# Diagram.net
KiCad netlist of a schematic drawn in EAGLE
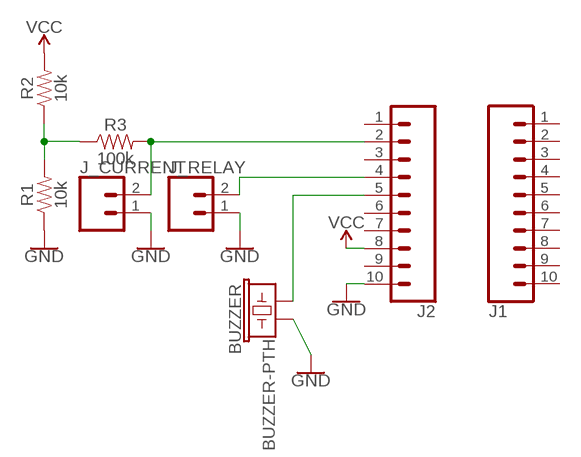
[diagram p0: schematic, sheet 1]

(export (version "E")
  (design (tool "Eeschema 10.0.6"))
  (components
    (comp (ref "BUZZER")
      (value "BUZZER-PTH")
      (footprint "eagle-import:BUZZER-12MM")
      (libsource (lib "eagle-import") (part "BUZZER-PTH"))
    )
    (comp (ref "J1")
      (value "CONN_10\"")
      (footprint "eagle-import:1X10")
      (libsource (lib "eagle-import") (part "CONN_10{dblquote}"))
    )
    (comp (ref "J2")
      (value "CONN_10\"")
      (footprint "eagle-import:1X10")
      (libsource (lib "eagle-import") (part "CONN_10{dblquote}"))
    )
    (comp (ref "J_CURRENT")
      (value "CONN_02")
      (footprint "eagle-import:1X02")
      (libsource (lib "eagle-import") (part "CONN_02"))
    )
    (comp (ref "J_RELAY")
      (value "CONN_02")
      (footprint "eagle-import:1X02")
      (libsource (lib "eagle-import") (part "CONN_02"))
    )
    (comp (ref "R1")
      (value "10k")
      (footprint "eagle-import:AXIAL-0.3")
      (libsource (lib "eagle-import") (part "1KOHM-HORIZ-1/4W-1%"))
    )
    (comp (ref "R2")
      (value "10k")
      (footprint "eagle-import:AXIAL-0.3")
      (libsource (lib "eagle-import") (part "1KOHM-HORIZ-1/4W-1%"))
    )
    (comp (ref "R3")
      (value "100k")
      (footprint "eagle-import:AXIAL-0.3")
      (libsource (lib "eagle-import") (part "1KOHM-HORIZ-1/4W-1%"))
    )
  )
  (nets
    (net (code "1") (name "GND") (class "Default")
      (node (ref "BUZZER") (pin "-") (pinfunction "2_-") (pintype "passive"))
      (node (ref "J2") (pin "10") (pinfunction "10_10") (pintype "passive"))
      (node (ref "J_CURRENT") (pin "1") (pinfunction "1_1") (pintype "passive"))
      (node (ref "J_RELAY") (pin "1") (pinfunction "1_1") (pintype "passive"))
      (node (ref "R1") (pin "P$1") (pinfunction "1_P$1") (pintype "passive"))
    )
    (net (code "2") (name "Net-(BUZZER-1)") (class "Default")
      (node (ref "BUZZER") (pin "+") (pinfunction "1_+") (pintype "passive"))
      (node (ref "J2") (pin "5") (pinfunction "5_5") (pintype "passive"))
    )
    (net (code "3") (name "Net-(J2-Pad4)") (class "Default")
      (node (ref "J2") (pin "4") (pinfunction "4_4") (pintype "passive"))
      (node (ref "J_RELAY") (pin "2") (pinfunction "2_2") (pintype "passive"))
    )
    (net (code "4") (name "Net-(R1-2)") (class "Default")
      (node (ref "R1") (pin "P$2") (pinfunction "2_P$2") (pintype "passive"))
      (node (ref "R2") (pin "P$1") (pinfunction "1_P$1") (pintype "passive"))
      (node (ref "R3") (pin "P$1") (pinfunction "1_P$1") (pintype "passive"))
    )
    (net (code "5") (name "Net-(R3-2)") (class "Default")
      (node (ref "J2") (pin "2") (pinfunction "2_2") (pintype "passive"))
      (node (ref "J_CURRENT") (pin "2") (pinfunction "2_2") (pintype "passive"))
      (node (ref "R3") (pin "P$2") (pinfunction "2_P$2") (pintype "passive"))
    )
    (net (code "6") (name "VCC") (class "Default")
      (node (ref "J2") (pin "8") (pinfunction "8_8") (pintype "passive"))
      (node (ref "R2") (pin "P$2") (pinfunction "2_P$2") (pintype "passive"))
    )
    (net (code "7") (name "unconnected-(J1-Pad1)") (class "Default")
      (node (ref "J1") (pin "1") (pinfunction "1_1") (pintype "passive"))
    )
    (net (code "8") (name "unconnected-(J1-Pad2)") (class "Default")
      (node (ref "J1") (pin "2") (pinfunction "2_2") (pintype "passive"))
    )
    (net (code "9") (name "unconnected-(J1-Pad3)") (class "Default")
      (node (ref "J1") (pin "3") (pinfunction "3_3") (pintype "passive"))
    )
    (net (code "10") (name "unconnected-(J1-Pad4)") (class "Default")
      (node (ref "J1") (pin "4") (pinfunction "4_4") (pintype "passive"))
    )
    (net (code "11") (name "unconnected-(J1-Pad5)") (class "Default")
      (node (ref "J1") (pin "5") (pinfunction "5_5") (pintype "passive"))
    )
    (net (code "12") (name "unconnected-(J1-Pad6)") (class "Default")
      (node (ref "J1") (pin "6") (pinfunction "6_6") (pintype "passive"))
    )
    (net (code "13") (name "unconnected-(J1-Pad7)") (class "Default")
      (node (ref "J1") (pin "7") (pinfunction "7_7") (pintype "passive"))
    )
    (net (code "14") (name "unconnected-(J1-Pad8)") (class "Default")
      (node (ref "J1") (pin "8") (pinfunction "8_8") (pintype "passive"))
    )
    (net (code "15") (name "unconnected-(J1-Pad9)") (class "Default")
      (node (ref "J1") (pin "9") (pinfunction "9_9") (pintype "passive"))
    )
    (net (code "16") (name "unconnected-(J1-Pad10)") (class "Default")
      (node (ref "J1") (pin "10") (pinfunction "10_10") (pintype "passive"))
    )
    (net (code "17") (name "unconnected-(J2-Pad1)") (class "Default")
      (node (ref "J2") (pin "1") (pinfunction "1_1") (pintype "passive"))
    )
    (net (code "18") (name "unconnected-(J2-Pad3)") (class "Default")
      (node (ref "J2") (pin "3") (pinfunction "3_3") (pintype "passive"))
    )
    (net (code "19") (name "unconnected-(J2-Pad6)") (class "Default")
      (node (ref "J2") (pin "6") (pinfunction "6_6") (pintype "passive"))
    )
    (net (code "20") (name "unconnected-(J2-Pad7)") (class "Default")
      (node (ref "J2") (pin "7") (pinfunction "7_7") (pintype "passive"))
    )
    (net (code "21") (name "unconnected-(J2-Pad9)") (class "Default")
      (node (ref "J2") (pin "9") (pinfunction "9_9") (pintype "passive"))
    )
  )
)
